# Multiply_2.net
KiCad netlist of a schematic drawn in Altium Designer
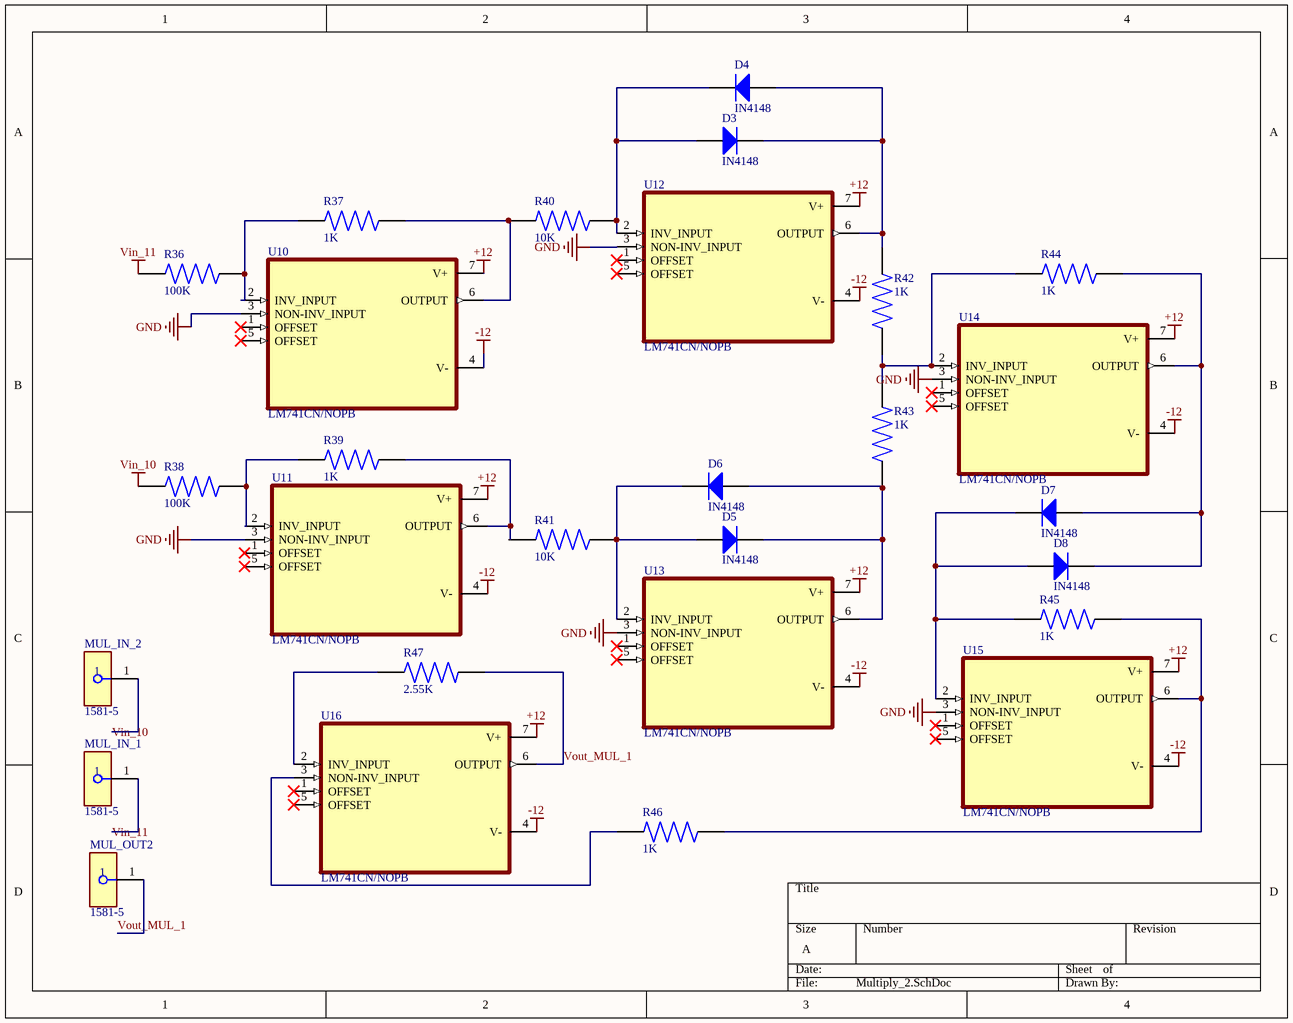
[diagram p0: Multiply_2.SchDoc]

(export (version "E")
  (design (tool "Eeschema 10.0.6"))
  (components
    (comp (ref "D3")
      (value "IN4148")
      (footprint "PCBComponent_1")
      (libsource (lib "Integrated_Library2") (part "Component_1"))
    )
    (comp (ref "D4")
      (value "IN4148")
      (footprint "PCBComponent_1")
      (libsource (lib "Integrated_Library2") (part "Component_1"))
    )
    (comp (ref "D5")
      (value "IN4148")
      (footprint "PCBComponent_1")
      (libsource (lib "Integrated_Library2") (part "Component_1"))
    )
    (comp (ref "D6")
      (value "IN4148")
      (footprint "PCBComponent_1")
      (libsource (lib "Integrated_Library2") (part "Component_1"))
    )
    (comp (ref "D7")
      (value "IN4148")
      (footprint "PCBComponent_1")
      (libsource (lib "Integrated_Library2") (part "Component_1"))
    )
    (comp (ref "D8")
      (value "IN4148")
      (footprint "PCBComponent_1")
      (libsource (lib "Integrated_Library2") (part "Component_1"))
    )
    (comp (ref "MUL_IN_1")
      (value "1581-5")
      (footprint "FP-1581-5-MFG")
      (description "CONN BANANA JACK TURRET GREEN")
      (libsource (lib "Altium Content Vault") (part "c5c826e0c4b67fe3b42ef77f2d4decc"))
    )
    (comp (ref "MUL_IN_2")
      (value "1581-5")
      (footprint "FP-1581-5-MFG")
      (description "CONN BANANA JACK TURRET GREEN")
      (libsource (lib "Altium Content Vault") (part "c5c826e0c4b67fe3b42ef77f2d4decc"))
    )
    (comp (ref "MUL_OUT2")
      (value "1581-5")
      (footprint "FP-1581-5-MFG")
      (description "CONN BANANA JACK TURRET GREEN")
      (libsource (lib "Altium Content Vault") (part "c5c826e0c4b67fe3b42ef77f2d4decc"))
    )
    (comp (ref "R36")
      (value "100K")
      (footprint "RESAD1100W55L680D260")
      (description "1.07 kOhms Â±1% 0.25W, 1/4W Through Hole Resistor Axial - Metal Film")
      (fields (field (name "MF") "Yageo") (field (name "MP") "MFR-25FBF52-1K"))
      (libsource (lib "MFR-25FBF52-1K") (part "MFR-25FBF52-1K"))
    )
    (comp (ref "R37")
      (value "1K")
      (footprint "RESAD1100W55L680D260")
      (description "1.07 kOhms Â±1% 0.25W, 1/4W Through Hole Resistor Axial - Metal Film")
      (fields (field (name "MF") "Yageo") (field (name "MP") "MFR-25FBF52-1K"))
      (libsource (lib "MFR-25FBF52-1K") (part "MFR-25FBF52-1K"))
    )
    (comp (ref "R38")
      (value "100K")
      (footprint "RESAD1100W55L680D260")
      (description "1.07 kOhms Â±1% 0.25W, 1/4W Through Hole Resistor Axial - Metal Film")
      (fields (field (name "MF") "Yageo") (field (name "MP") "MFR-25FBF52-1K"))
      (libsource (lib "MFR-25FBF52-1K") (part "MFR-25FBF52-1K"))
    )
    (comp (ref "R39")
      (value "1K")
      (footprint "RESAD1100W55L680D260")
      (description "1.07 kOhms Â±1% 0.25W, 1/4W Through Hole Resistor Axial - Metal Film")
      (fields (field (name "MF") "Yageo") (field (name "MP") "MFR-25FBF52-1K"))
      (libsource (lib "MFR-25FBF52-1K") (part "MFR-25FBF52-1K"))
    )
    (comp (ref "R40")
      (value "10K")
      (footprint "RESAD1100W55L680D260")
      (description "1.07 kOhms Â±1% 0.25W, 1/4W Through Hole Resistor Axial - Metal Film")
      (fields (field (name "MF") "Yageo") (field (name "MP") "MFR-25FBF52-1K"))
      (libsource (lib "MFR-25FBF52-1K") (part "MFR-25FBF52-1K"))
    )
    (comp (ref "R41")
      (value "10K")
      (footprint "RESAD1100W55L680D260")
      (description "1.07 kOhms Â±1% 0.25W, 1/4W Through Hole Resistor Axial - Metal Film")
      (fields (field (name "MF") "Yageo") (field (name "MP") "MFR-25FBF52-1K"))
      (libsource (lib "MFR-25FBF52-1K") (part "MFR-25FBF52-1K"))
    )
    (comp (ref "R42")
      (value "1K")
      (footprint "RESAD1100W55L680D260")
      (description "1.07 kOhms Â±1% 0.25W, 1/4W Through Hole Resistor Axial - Metal Film")
      (fields (field (name "MF") "Yageo") (field (name "MP") "MFR-25FBF52-1K"))
      (libsource (lib "MFR-25FBF52-1K") (part "MFR-25FBF52-1K"))
    )
    (comp (ref "R43")
      (value "1K")
      (footprint "RESAD1100W55L680D260")
      (description "1.07 kOhms Â±1% 0.25W, 1/4W Through Hole Resistor Axial - Metal Film")
      (fields (field (name "MF") "Yageo") (field (name "MP") "MFR-25FBF52-1K"))
      (libsource (lib "MFR-25FBF52-1K") (part "MFR-25FBF52-1K"))
    )
    (comp (ref "R44")
      (value "1K")
      (footprint "RESAD1100W55L680D260")
      (description "1.07 kOhms Â±1% 0.25W, 1/4W Through Hole Resistor Axial - Metal Film")
      (fields (field (name "MF") "Yageo") (field (name "MP") "MFR-25FBF52-1K"))
      (libsource (lib "MFR-25FBF52-1K") (part "MFR-25FBF52-1K"))
    )
    (comp (ref "R45")
      (value "1K")
      (footprint "RESAD1100W55L680D260")
      (description "1.07 kOhms Â±1% 0.25W, 1/4W Through Hole Resistor Axial - Metal Film")
      (fields (field (name "MF") "Yageo") (field (name "MP") "MFR-25FBF52-1K"))
      (libsource (lib "MFR-25FBF52-1K") (part "MFR-25FBF52-1K"))
    )
    (comp (ref "R46")
      (value "1K")
      (footprint "RESAD1100W55L680D260")
      (description "1.07 kOhms Â±1% 0.25W, 1/4W Through Hole Resistor Axial - Metal Film")
      (fields (field (name "MF") "Yageo") (field (name "MP") "MFR-25FBF52-1K"))
      (libsource (lib "MFR-25FBF52-1K") (part "MFR-25FBF52-1K"))
    )
    (comp (ref "R47")
      (value "2.55K")
      (footprint "RESAD1100W55L680D260")
      (description "1.07 kOhms Â±1% 0.25W, 1/4W Through Hole Resistor Axial - Metal Film")
      (fields (field (name "MF") "Yageo") (field (name "MP") "MFR-25FBF52-1K"))
      (libsource (lib "MFR-25FBF52-1K") (part "MFR-25FBF52-1K"))
    )
    (comp (ref "U10")
      (value "LM741CN/NOPB")
      (footprint "DIP794W45P254L959H508Q8")
      (description "Single, 44-V, 1-MHz operational amplifier")
      (fields (field (name "MF") "Texas Instruments"))
      (libsource (lib "LM741CN_NOPB (1)") (part "LM741CN/NOPB"))
    )
    (comp (ref "U11")
      (value "LM741CN/NOPB")
      (footprint "DIP794W45P254L959H508Q8")
      (description "Single, 44-V, 1-MHz operational amplifier")
      (fields (field (name "MF") "Texas Instruments"))
      (libsource (lib "LM741CN_NOPB (1)") (part "LM741CN/NOPB"))
    )
    (comp (ref "U12")
      (value "LM741CN/NOPB")
      (footprint "DIP794W45P254L959H508Q8")
      (description "Single, 44-V, 1-MHz operational amplifier")
      (fields (field (name "MF") "Texas Instruments"))
      (libsource (lib "LM741CN_NOPB (1)") (part "LM741CN/NOPB"))
    )
    (comp (ref "U13")
      (value "LM741CN/NOPB")
      (footprint "DIP794W45P254L959H508Q8")
      (description "Single, 44-V, 1-MHz operational amplifier")
      (fields (field (name "MF") "Texas Instruments"))
      (libsource (lib "LM741CN_NOPB (1)") (part "LM741CN/NOPB"))
    )
    (comp (ref "U14")
      (value "LM741CN/NOPB")
      (footprint "DIP794W45P254L959H508Q8")
      (description "Single, 44-V, 1-MHz operational amplifier")
      (fields (field (name "MF") "Texas Instruments"))
      (libsource (lib "LM741CN_NOPB (1)") (part "LM741CN/NOPB"))
    )
    (comp (ref "U15")
      (value "LM741CN/NOPB")
      (footprint "DIP794W45P254L959H508Q8")
      (description "Single, 44-V, 1-MHz operational amplifier")
      (fields (field (name "MF") "Texas Instruments"))
      (libsource (lib "LM741CN_NOPB (1)") (part "LM741CN/NOPB"))
    )
    (comp (ref "U16")
      (value "LM741CN/NOPB")
      (footprint "DIP794W45P254L959H508Q8")
      (description "Single, 44-V, 1-MHz operational amplifier")
      (fields (field (name "MF") "Texas Instruments"))
      (libsource (lib "LM741CN_NOPB (1)") (part "LM741CN/NOPB"))
    )
  )
  (nets
    (net (code "1") (name "+12") (class "Default")
      (node (ref "U10") (pin "7") (pinfunction "V+_7") (pintype "power_in"))
      (node (ref "U11") (pin "7") (pinfunction "V+_7") (pintype "power_in"))
      (node (ref "U12") (pin "7") (pinfunction "V+_7") (pintype "power_in"))
      (node (ref "U13") (pin "7") (pinfunction "V+_7") (pintype "power_in"))
      (node (ref "U14") (pin "7") (pinfunction "V+_7") (pintype "power_in"))
      (node (ref "U15") (pin "7") (pinfunction "V+_7") (pintype "power_in"))
      (node (ref "U16") (pin "7") (pinfunction "V+_7") (pintype "power_in"))
    )
    (net (code "2") (name "-12") (class "Default")
      (node (ref "U10") (pin "4") (pinfunction "V-_4") (pintype "power_in"))
      (node (ref "U11") (pin "4") (pinfunction "V-_4") (pintype "power_in"))
      (node (ref "U12") (pin "4") (pinfunction "V-_4") (pintype "power_in"))
      (node (ref "U13") (pin "4") (pinfunction "V-_4") (pintype "power_in"))
      (node (ref "U14") (pin "4") (pinfunction "V-_4") (pintype "power_in"))
      (node (ref "U15") (pin "4") (pinfunction "V-_4") (pintype "power_in"))
      (node (ref "U16") (pin "4") (pinfunction "V-_4") (pintype "power_in"))
    )
    (net (code "3") (name "/Vout_MUL_1") (class "Default")
      (node (ref "MUL_OUT2") (pin "1") (pinfunction "1_1") (pintype "passive"))
      (node (ref "R47") (pin "2") (pinfunction "2_2") (pintype "passive"))
      (node (ref "U16") (pin "6") (pinfunction "OUTPUT_6") (pintype "output"))
    )
    (net (code "4") (name "GND") (class "Default")
      (node (ref "U10") (pin "3") (pinfunction "NON-INV_INPUT_3") (pintype "input"))
      (node (ref "U11") (pin "3") (pinfunction "NON-INV_INPUT_3") (pintype "input"))
      (node (ref "U12") (pin "3") (pinfunction "NON-INV_INPUT_3") (pintype "input"))
      (node (ref "U13") (pin "3") (pinfunction "NON-INV_INPUT_3") (pintype "input"))
      (node (ref "U14") (pin "3") (pinfunction "NON-INV_INPUT_3") (pintype "input"))
      (node (ref "U15") (pin "3") (pinfunction "NON-INV_INPUT_3") (pintype "input"))
    )
    (net (code "5") (name "Net-(D3-A)") (class "Default")
      (node (ref "D3") (pin "2") (pinfunction "A_2") (pintype "passive"))
      (node (ref "D4") (pin "1") (pinfunction "K_1") (pintype "passive"))
      (node (ref "R40") (pin "2") (pinfunction "2_2") (pintype "passive"))
      (node (ref "U12") (pin "2") (pinfunction "INV_INPUT_2") (pintype "input"))
    )
    (net (code "6") (name "Net-(D3-K)") (class "Default")
      (node (ref "D3") (pin "1") (pinfunction "K_1") (pintype "passive"))
      (node (ref "D4") (pin "2") (pinfunction "A_2") (pintype "passive"))
      (node (ref "R42") (pin "1") (pinfunction "1_1") (pintype "passive"))
      (node (ref "U12") (pin "6") (pinfunction "OUTPUT_6") (pintype "output"))
    )
    (net (code "7") (name "Net-(D5-A)") (class "Default")
      (node (ref "D5") (pin "2") (pinfunction "A_2") (pintype "passive"))
      (node (ref "D6") (pin "1") (pinfunction "K_1") (pintype "passive"))
      (node (ref "R41") (pin "2") (pinfunction "2_2") (pintype "passive"))
      (node (ref "U13") (pin "2") (pinfunction "INV_INPUT_2") (pintype "input"))
    )
    (net (code "8") (name "Net-(D5-K)") (class "Default")
      (node (ref "D5") (pin "1") (pinfunction "K_1") (pintype "passive"))
      (node (ref "D6") (pin "2") (pinfunction "A_2") (pintype "passive"))
      (node (ref "R43") (pin "1") (pinfunction "1_1") (pintype "passive"))
      (node (ref "U13") (pin "6") (pinfunction "OUTPUT_6") (pintype "output"))
    )
    (net (code "9") (name "Net-(D7-A)") (class "Default")
      (node (ref "D7") (pin "2") (pinfunction "A_2") (pintype "passive"))
      (node (ref "D8") (pin "1") (pinfunction "K_1") (pintype "passive"))
      (node (ref "R44") (pin "2") (pinfunction "2_2") (pintype "passive"))
      (node (ref "U14") (pin "6") (pinfunction "OUTPUT_6") (pintype "output"))
    )
    (net (code "10") (name "Net-(D7-K)") (class "Default")
      (node (ref "D7") (pin "1") (pinfunction "K_1") (pintype "passive"))
      (node (ref "D8") (pin "2") (pinfunction "A_2") (pintype "passive"))
      (node (ref "R45") (pin "1") (pinfunction "1_1") (pintype "passive"))
      (node (ref "U15") (pin "2") (pinfunction "INV_INPUT_2") (pintype "input"))
    )
    (net (code "11") (name "Net-(U10-INV_INPUT)") (class "Default")
      (node (ref "R36") (pin "2") (pinfunction "2_2") (pintype "passive"))
      (node (ref "R37") (pin "1") (pinfunction "1_1") (pintype "passive"))
      (node (ref "U10") (pin "2") (pinfunction "INV_INPUT_2") (pintype "input"))
    )
    (net (code "12") (name "Net-(U10-OUTPUT)") (class "Default")
      (node (ref "R37") (pin "2") (pinfunction "2_2") (pintype "passive"))
      (node (ref "R40") (pin "1") (pinfunction "1_1") (pintype "passive"))
      (node (ref "U10") (pin "6") (pinfunction "OUTPUT_6") (pintype "output"))
    )
    (net (code "13") (name "Net-(U11-INV_INPUT)") (class "Default")
      (node (ref "R38") (pin "2") (pinfunction "2_2") (pintype "passive"))
      (node (ref "R39") (pin "1") (pinfunction "1_1") (pintype "passive"))
      (node (ref "U11") (pin "2") (pinfunction "INV_INPUT_2") (pintype "input"))
    )
    (net (code "14") (name "Net-(U11-OUTPUT)") (class "Default")
      (node (ref "R39") (pin "2") (pinfunction "2_2") (pintype "passive"))
      (node (ref "U11") (pin "6") (pinfunction "OUTPUT_6") (pintype "output"))
    )
    (net (code "15") (name "Net-(U14-INV_INPUT)") (class "Default")
      (node (ref "R42") (pin "2") (pinfunction "2_2") (pintype "passive"))
      (node (ref "R43") (pin "2") (pinfunction "2_2") (pintype "passive"))
      (node (ref "R44") (pin "1") (pinfunction "1_1") (pintype "passive"))
      (node (ref "U14") (pin "2") (pinfunction "INV_INPUT_2") (pintype "input"))
    )
    (net (code "16") (name "Net-(U15-OUTPUT)") (class "Default")
      (node (ref "R45") (pin "2") (pinfunction "2_2") (pintype "passive"))
      (node (ref "R46") (pin "2") (pinfunction "2_2") (pintype "passive"))
      (node (ref "U15") (pin "6") (pinfunction "OUTPUT_6") (pintype "output"))
    )
    (net (code "17") (name "Net-(U16-INV_INPUT)") (class "Default")
      (node (ref "R47") (pin "1") (pinfunction "1_1") (pintype "passive"))
      (node (ref "U16") (pin "2") (pinfunction "INV_INPUT_2") (pintype "input"))
    )
    (net (code "18") (name "Net-(U16-NON-INV_INPUT)") (class "Default")
      (node (ref "R46") (pin "1") (pinfunction "1_1") (pintype "passive"))
      (node (ref "U16") (pin "3") (pinfunction "NON-INV_INPUT_3") (pintype "input"))
    )
    (net (code "19") (name "Vin_10") (class "Default")
      (node (ref "MUL_IN_2") (pin "1") (pinfunction "1_1") (pintype "passive"))
      (node (ref "R38") (pin "1") (pinfunction "1_1") (pintype "passive"))
    )
    (net (code "20") (name "Vin_11") (class "Default")
      (node (ref "MUL_IN_1") (pin "1") (pinfunction "1_1") (pintype "passive"))
      (node (ref "R36") (pin "1") (pinfunction "1_1") (pintype "passive"))
    )
    (net (code "21") (name "unconnected-(R41-Pad1)") (class "Default")
      (node (ref "R41") (pin "1") (pinfunction "1_1") (pintype "passive"))
    )
    (net (code "22") (name "unconnected-(U10-OFFSET-Pad1)") (class "Default")
      (node (ref "U10") (pin "1") (pinfunction "OFFSET_1") (pintype "input+no_connect"))
    )
    (net (code "23") (name "unconnected-(U10-OFFSET-Pad5)") (class "Default")
      (node (ref "U10") (pin "5") (pinfunction "OFFSET_5") (pintype "input+no_connect"))
    )
    (net (code "24") (name "unconnected-(U11-OFFSET-Pad1)") (class "Default")
      (node (ref "U11") (pin "1") (pinfunction "OFFSET_1") (pintype "input+no_connect"))
    )
    (net (code "25") (name "unconnected-(U11-OFFSET-Pad5)") (class "Default")
      (node (ref "U11") (pin "5") (pinfunction "OFFSET_5") (pintype "input+no_connect"))
    )
    (net (code "26") (name "unconnected-(U12-OFFSET-Pad1)") (class "Default")
      (node (ref "U12") (pin "1") (pinfunction "OFFSET_1") (pintype "input+no_connect"))
    )
    (net (code "27") (name "unconnected-(U12-OFFSET-Pad5)") (class "Default")
      (node (ref "U12") (pin "5") (pinfunction "OFFSET_5") (pintype "input+no_connect"))
    )
    (net (code "28") (name "unconnected-(U13-OFFSET-Pad1)") (class "Default")
      (node (ref "U13") (pin "1") (pinfunction "OFFSET_1") (pintype "input+no_connect"))
    )
    (net (code "29") (name "unconnected-(U13-OFFSET-Pad5)") (class "Default")
      (node (ref "U13") (pin "5") (pinfunction "OFFSET_5") (pintype "input+no_connect"))
    )
    (net (code "30") (name "unconnected-(U14-OFFSET-Pad1)") (class "Default")
      (node (ref "U14") (pin "1") (pinfunction "OFFSET_1") (pintype "input+no_connect"))
    )
    (net (code "31") (name "unconnected-(U14-OFFSET-Pad5)") (class "Default")
      (node (ref "U14") (pin "5") (pinfunction "OFFSET_5") (pintype "input+no_connect"))
    )
    (net (code "32") (name "unconnected-(U15-OFFSET-Pad1)") (class "Default")
      (node (ref "U15") (pin "1") (pinfunction "OFFSET_1") (pintype "input+no_connect"))
    )
    (net (code "33") (name "unconnected-(U15-OFFSET-Pad5)") (class "Default")
      (node (ref "U15") (pin "5") (pinfunction "OFFSET_5") (pintype "input+no_connect"))
    )
    (net (code "34") (name "unconnected-(U16-OFFSET-Pad1)") (class "Default")
      (node (ref "U16") (pin "1") (pinfunction "OFFSET_1") (pintype "input+no_connect"))
    )
    (net (code "35") (name "unconnected-(U16-OFFSET-Pad5)") (class "Default")
      (node (ref "U16") (pin "5") (pinfunction "OFFSET_5") (pintype "input+no_connect"))
    )
  )
)
